# Voltage_Current_Schem.net
KiCad netlist of a schematic drawn in Altium Designer
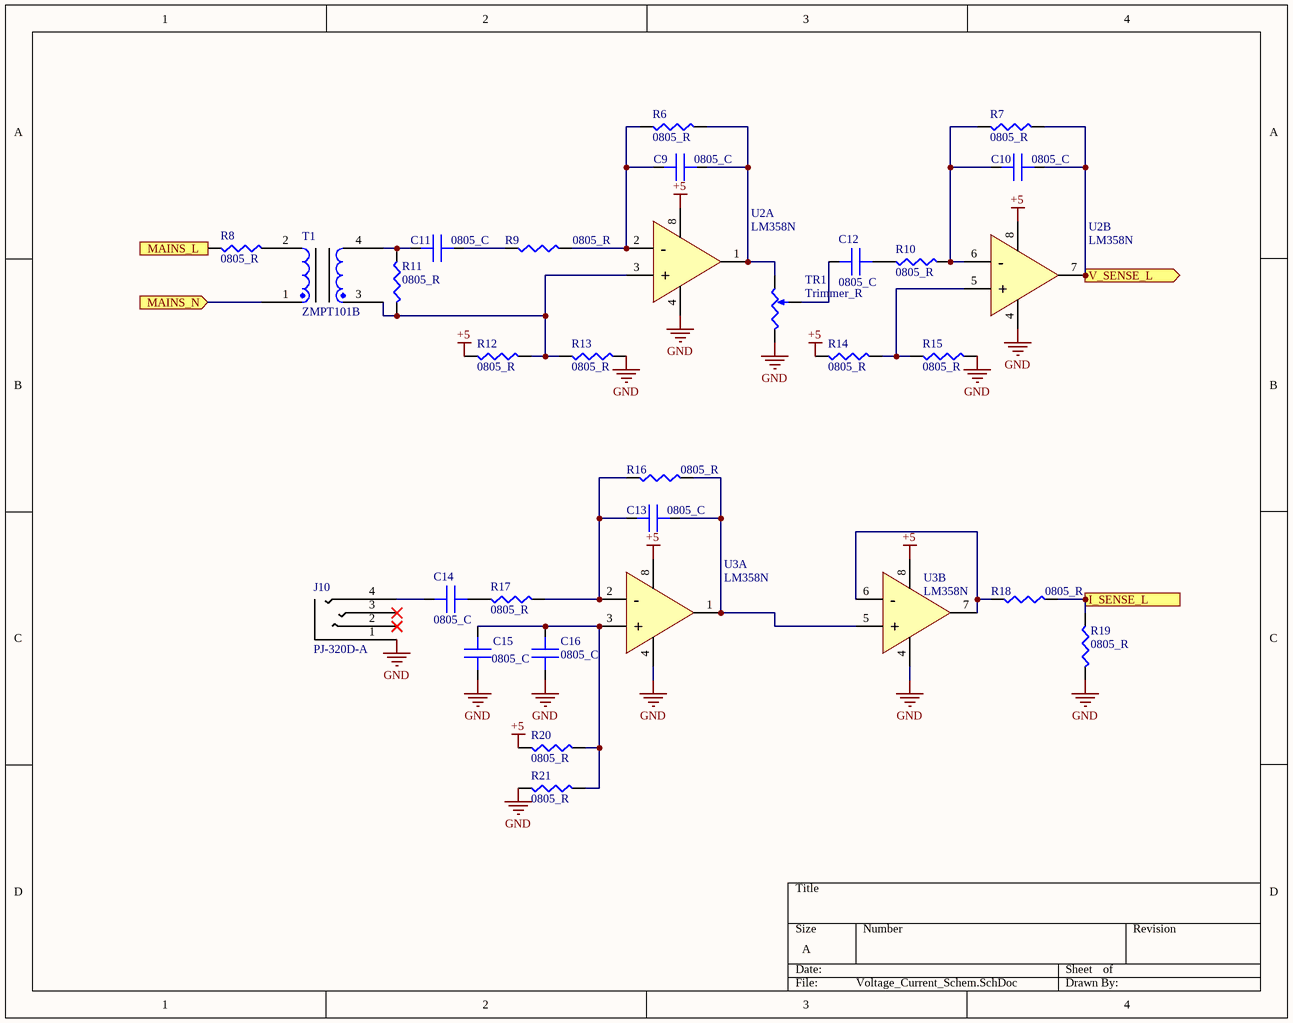
[diagram p0: Voltage_Current_Schem.SchDoc]

(export (version "E")
  (design (tool "Eeschema 10.0.6"))
  (components
    (comp (ref "C9")
      (value "0805_C")
      (footprint "C0805 - 0.1uf")
      (description "0805 Capacitor")
      (libsource (lib "TimerSMD_Components") (part "0805 Capacitor"))
    )
    (comp (ref "C10")
      (value "0805_C")
      (footprint "C0805 - 0.1uf")
      (description "0805 Capacitor")
      (libsource (lib "TimerSMD_Components") (part "0805 Capacitor"))
    )
    (comp (ref "C11")
      (value "0805_C")
      (footprint "C0805 - 0.1uf")
      (description "0805 Capacitor")
      (libsource (lib "TimerSMD_Components") (part "0805 Capacitor"))
    )
    (comp (ref "C12")
      (value "0805_C")
      (footprint "C0805 - 0.1uf")
      (description "0805 Capacitor")
      (libsource (lib "TimerSMD_Components") (part "0805 Capacitor"))
    )
    (comp (ref "C13")
      (value "0805_C")
      (footprint "C0805 - 0.1uf")
      (description "0805 Capacitor")
      (libsource (lib "TimerSMD_Components") (part "0805 Capacitor"))
    )
    (comp (ref "C14")
      (value "0805_C")
      (footprint "C0805 - 0.1uf")
      (description "0805 Capacitor")
      (libsource (lib "TimerSMD_Components") (part "0805 Capacitor"))
    )
    (comp (ref "C15")
      (value "0805_C")
      (footprint "C0805 - 0.1uf")
      (description "0805 Capacitor")
      (libsource (lib "TimerSMD_Components") (part "0805 Capacitor"))
    )
    (comp (ref "C16")
      (value "0805_C")
      (footprint "C0805 - 0.1uf")
      (description "0805 Capacitor")
      (libsource (lib "TimerSMD_Components") (part "0805 Capacitor"))
    )
    (comp (ref "J10")
      (value "PJ-320D-A")
      (footprint "PJ-320D-A")
      (libsource (lib "EV_Symbols") (part "PJ-320D-A"))
    )
    (comp (ref "R6")
      (value "0805_R")
      (footprint "R0805")
      (libsource (lib "TimerSMD_Components") (part "0805 Resistor"))
    )
    (comp (ref "R7")
      (value "0805_R")
      (footprint "R0805")
      (libsource (lib "TimerSMD_Components") (part "0805 Resistor"))
    )
    (comp (ref "R8")
      (value "0805_R")
      (footprint "R0805")
      (libsource (lib "TimerSMD_Components") (part "0805 Resistor"))
    )
    (comp (ref "R9")
      (value "0805_R")
      (footprint "R0805")
      (libsource (lib "TimerSMD_Components") (part "0805 Resistor"))
    )
    (comp (ref "R10")
      (value "0805_R")
      (footprint "R0805")
      (libsource (lib "TimerSMD_Components") (part "0805 Resistor"))
    )
    (comp (ref "R11")
      (value "0805_R")
      (footprint "R0805")
      (libsource (lib "TimerSMD_Components") (part "0805 Resistor"))
    )
    (comp (ref "R12")
      (value "0805_R")
      (footprint "R0805")
      (libsource (lib "TimerSMD_Components") (part "0805 Resistor"))
    )
    (comp (ref "R13")
      (value "0805_R")
      (footprint "R0805")
      (libsource (lib "TimerSMD_Components") (part "0805 Resistor"))
    )
    (comp (ref "R14")
      (value "0805_R")
      (footprint "R0805")
      (libsource (lib "TimerSMD_Components") (part "0805 Resistor"))
    )
    (comp (ref "R15")
      (value "0805_R")
      (footprint "R0805")
      (libsource (lib "TimerSMD_Components") (part "0805 Resistor"))
    )
    (comp (ref "R16")
      (value "0805_R")
      (footprint "R0805")
      (libsource (lib "TimerSMD_Components") (part "0805 Resistor"))
    )
    (comp (ref "R17")
      (value "0805_R")
      (footprint "R0805")
      (libsource (lib "TimerSMD_Components") (part "0805 Resistor"))
    )
    (comp (ref "R18")
      (value "0805_R")
      (footprint "R0805")
      (libsource (lib "TimerSMD_Components") (part "0805 Resistor"))
    )
    (comp (ref "R19")
      (value "0805_R")
      (footprint "R0805")
      (libsource (lib "TimerSMD_Components") (part "0805 Resistor"))
    )
    (comp (ref "R20")
      (value "0805_R")
      (footprint "R0805")
      (libsource (lib "TimerSMD_Components") (part "0805 Resistor"))
    )
    (comp (ref "R21")
      (value "0805_R")
      (footprint "R0805")
      (libsource (lib "TimerSMD_Components") (part "0805 Resistor"))
    )
    (comp (ref "T1")
      (value "ZMPT101B")
      (footprint "ZMPT101B")
      (libsource (lib "EV_Symbols") (part "ZMPT101B"))
    )
    (comp (ref "TR1")
      (value "Trimmer_R")
      (footprint "3296W_TRIMMER")
      (libsource (lib "CAD_Symbols") (part "Blue Trimmer Pot (Small)"))
    )
    (comp (ref "U2") (value "LM358N") (footprint "SOP8") (libsource (lib "EV_Symbols") (part "LM358N")))
    (comp (ref "U3") (value "LM358N") (footprint "SOP8") (libsource (lib "EV_Symbols") (part "LM358N")))
  )
  (nets
    (net (code "1") (name "+5") (class "Default")
      (node (ref "R12") (pin "1") (pinfunction "1_1") (pintype "passive"))
      (node (ref "R14") (pin "1") (pinfunction "1_1") (pintype "passive"))
      (node (ref "R20") (pin "2") (pinfunction "2_2") (pintype "passive"))
      (node (ref "U2") (pin "8") (pinfunction "VCC_8") (pintype "passive"))
      (node (ref "U3") (pin "8") (pinfunction "VCC_8") (pintype "passive"))
    )
    (net (code "2") (name "/I_SENSE_L") (class "Default")
      (node (ref "R18") (pin "1") (pinfunction "1_1") (pintype "passive"))
      (node (ref "R19") (pin "1") (pinfunction "1_1") (pintype "passive"))
    )
    (net (code "3") (name "/MAINS_L") (class "Default")
      (node (ref "R8") (pin "1") (pinfunction "1_1") (pintype "passive"))
    )
    (net (code "4") (name "/MAINS_N") (class "Default")
      (node (ref "T1") (pin "1") (pinfunction "1_1") (pintype "passive"))
    )
    (net (code "5") (name "/V_SENSE_L") (class "Default")
      (node (ref "C10") (pin "2") (pinfunction "2_2") (pintype "passive"))
      (node (ref "R7") (pin "2") (pinfunction "2_2") (pintype "passive"))
      (node (ref "U2") (pin "7") (pinfunction "OUT1_7") (pintype "passive"))
    )
    (net (code "6") (name "GND") (class "Default")
      (node (ref "C15") (pin "1") (pinfunction "1_1") (pintype "passive"))
      (node (ref "C16") (pin "1") (pinfunction "1_1") (pintype "passive"))
      (node (ref "J10") (pin "1") (pinfunction "1_1") (pintype "passive"))
      (node (ref "R13") (pin "2") (pinfunction "2_2") (pintype "passive"))
      (node (ref "R15") (pin "2") (pinfunction "2_2") (pintype "passive"))
      (node (ref "R19") (pin "2") (pinfunction "2_2") (pintype "passive"))
      (node (ref "R21") (pin "2") (pinfunction "2_2") (pintype "passive"))
      (node (ref "TR1") (pin "2") (pinfunction "2_2") (pintype "passive"))
      (node (ref "U2") (pin "4") (pinfunction "VSS_4") (pintype "passive"))
      (node (ref "U3") (pin "4") (pinfunction "VSS_4") (pintype "passive"))
    )
    (net (code "7") (name "Net-(C11-Pad1)") (class "Default")
      (node (ref "C11") (pin "1") (pinfunction "1_1") (pintype "passive"))
      (node (ref "R11") (pin "2") (pinfunction "2_2") (pintype "passive"))
      (node (ref "T1") (pin "4") (pinfunction "4_4") (pintype "passive"))
    )
    (net (code "8") (name "Net-(C11-Pad2)") (class "Default")
      (node (ref "C11") (pin "2") (pinfunction "2_2") (pintype "passive"))
      (node (ref "R9") (pin "1") (pinfunction "1_1") (pintype "passive"))
    )
    (net (code "9") (name "Net-(C12-Pad1)") (class "Default")
      (node (ref "C12") (pin "1") (pinfunction "1_1") (pintype "passive"))
      (node (ref "TR1") (pin "3") (pinfunction "3_3") (pintype "passive"))
    )
    (net (code "10") (name "Net-(C12-Pad2)") (class "Default")
      (node (ref "C12") (pin "2") (pinfunction "2_2") (pintype "passive"))
      (node (ref "R10") (pin "1") (pinfunction "1_1") (pintype "passive"))
    )
    (net (code "11") (name "Net-(C14-Pad1)") (class "Default")
      (node (ref "C14") (pin "1") (pinfunction "1_1") (pintype "passive"))
      (node (ref "J10") (pin "4") (pinfunction "4_4") (pintype "passive"))
    )
    (net (code "12") (name "Net-(C14-Pad2)") (class "Default")
      (node (ref "C14") (pin "2") (pinfunction "2_2") (pintype "passive"))
      (node (ref "R17") (pin "2") (pinfunction "2_2") (pintype "passive"))
    )
    (net (code "13") (name "Net-(R8-Pad2)") (class "Default")
      (node (ref "R8") (pin "2") (pinfunction "2_2") (pintype "passive"))
      (node (ref "T1") (pin "2") (pinfunction "2_2") (pintype "passive"))
    )
    (net (code "14") (name "Net-(U2A-+)") (class "Default")
      (node (ref "R11") (pin "1") (pinfunction "1_1") (pintype "passive"))
      (node (ref "R12") (pin "2") (pinfunction "2_2") (pintype "passive"))
      (node (ref "R13") (pin "1") (pinfunction "1_1") (pintype "passive"))
      (node (ref "T1") (pin "3") (pinfunction "3_3") (pintype "passive"))
      (node (ref "U2") (pin "3") (pinfunction "+_3") (pintype "passive"))
    )
    (net (code "15") (name "Net-(U2A--)") (class "Default")
      (node (ref "C9") (pin "1") (pinfunction "1_1") (pintype "passive"))
      (node (ref "R6") (pin "1") (pinfunction "1_1") (pintype "passive"))
      (node (ref "R9") (pin "2") (pinfunction "2_2") (pintype "passive"))
      (node (ref "U2") (pin "2") (pinfunction "-_2") (pintype "passive"))
    )
    (net (code "16") (name "Net-(U2A-OUT1)") (class "Default")
      (node (ref "C9") (pin "2") (pinfunction "2_2") (pintype "passive"))
      (node (ref "R6") (pin "2") (pinfunction "2_2") (pintype "passive"))
      (node (ref "TR1") (pin "1") (pinfunction "1_1") (pintype "passive"))
      (node (ref "U2") (pin "1") (pinfunction "OUT1_1") (pintype "passive"))
    )
    (net (code "17") (name "Net-(U2B-+)") (class "Default")
      (node (ref "R14") (pin "2") (pinfunction "2_2") (pintype "passive"))
      (node (ref "R15") (pin "1") (pinfunction "1_1") (pintype "passive"))
      (node (ref "U2") (pin "5") (pinfunction "+_5") (pintype "passive"))
    )
    (net (code "18") (name "Net-(U2B--)") (class "Default")
      (node (ref "C10") (pin "1") (pinfunction "1_1") (pintype "passive"))
      (node (ref "R10") (pin "2") (pinfunction "2_2") (pintype "passive"))
      (node (ref "R7") (pin "1") (pinfunction "1_1") (pintype "passive"))
      (node (ref "U2") (pin "6") (pinfunction "-_6") (pintype "passive"))
    )
    (net (code "19") (name "Net-(U3A-+)") (class "Default")
      (node (ref "C15") (pin "2") (pinfunction "2_2") (pintype "passive"))
      (node (ref "C16") (pin "2") (pinfunction "2_2") (pintype "passive"))
      (node (ref "R20") (pin "1") (pinfunction "1_1") (pintype "passive"))
      (node (ref "R21") (pin "1") (pinfunction "1_1") (pintype "passive"))
      (node (ref "U3") (pin "3") (pinfunction "+_3") (pintype "passive"))
    )
    (net (code "20") (name "Net-(U3A--)") (class "Default")
      (node (ref "C13") (pin "1") (pinfunction "1_1") (pintype "passive"))
      (node (ref "R16") (pin "1") (pinfunction "1_1") (pintype "passive"))
      (node (ref "R17") (pin "1") (pinfunction "1_1") (pintype "passive"))
      (node (ref "U3") (pin "2") (pinfunction "-_2") (pintype "passive"))
    )
    (net (code "21") (name "Net-(U3A-OUT1)") (class "Default")
      (node (ref "C13") (pin "2") (pinfunction "2_2") (pintype "passive"))
      (node (ref "R16") (pin "2") (pinfunction "2_2") (pintype "passive"))
      (node (ref "U3") (pin "1") (pinfunction "OUT1_1") (pintype "passive"))
      (node (ref "U3") (pin "5") (pinfunction "+_5") (pintype "passive"))
    )
    (net (code "22") (name "Net-(U3B--)") (class "Default")
      (node (ref "R18") (pin "2") (pinfunction "2_2") (pintype "passive"))
      (node (ref "U3") (pin "6") (pinfunction "-_6") (pintype "passive"))
      (node (ref "U3") (pin "7") (pinfunction "OUT1_7") (pintype "passive"))
    )
    (net (code "23") (name "unconnected-(J10-Pad2)") (class "Default")
      (node (ref "J10") (pin "2") (pinfunction "2_2") (pintype "passive+no_connect"))
    )
    (net (code "24") (name "unconnected-(J10-Pad3)") (class "Default")
      (node (ref "J10") (pin "3") (pinfunction "3_3") (pintype "passive+no_connect"))
    )
  )
)
